# LEDs.net
KiCad netlist of a schematic drawn in Altium Designer
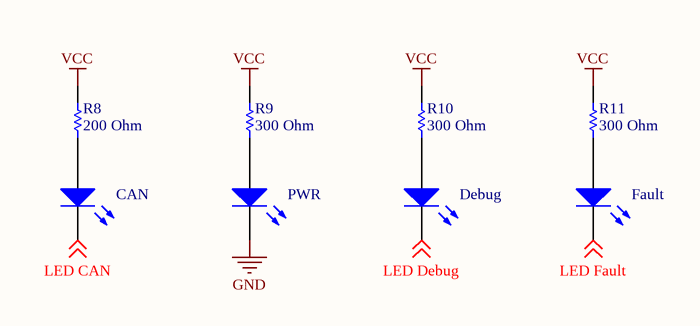
[diagram p0: LEDs.SchDoc]

(export (version "E")
  (design (tool "Eeschema 10.0.6"))
  (components
    (comp (ref "CAN")
      (value "LED")
      (footprint "0805_A")
      (description "Standard 0805 LED")
      (fields (field (name "MANUFACTURER") "Wuerth Elektronik") (field (name "PARTNUMBER") "150080SS75000"))
      (libsource (lib "Husky Robotics Standard Library 2019-2020") (part "LED"))
    )
    (comp (ref "Debug")
      (value "LED")
      (footprint "0805_A")
      (description "Standard 0805 LED")
      (libsource (lib "Husky Robotics Standard Library 2019-2020") (part "LED"))
    )
    (comp (ref "Fault")
      (value "LED")
      (footprint "0805_A")
      (description "Standard 0805 LED")
      (fields (field (name "MANUFACTURER") "Wuerth Elektronik") (field (name "PARTNUMBER") "150080SS75000"))
      (libsource (lib "Husky Robotics Standard Library 2019-2020") (part "LED"))
    )
    (comp (ref "PWR")
      (value "LED")
      (footprint "0805_A")
      (description "Standard 0805 LED")
      (libsource (lib "Husky Robotics Standard Library 2019-2020") (part "LED"))
    )
    (comp (ref "R8")
      (value "200 Ohm")
      (footprint "RESC0805(2012)_N")
      (description "Generic 0805 Resistor")
      (fields (field (name "TOLERANCE") "5 %") (field (name "POWER") "0.125 W"))
      (libsource (lib "Husky Robotics Standard Library 2019-2020") (part "Resistor 0805"))
    )
    (comp (ref "R9")
      (value "300 Ohm")
      (footprint "RESC0805(2012)_N")
      (description "Generic 0805 Resistor")
      (fields (field (name "TOLERANCE") "5 %") (field (name "POWER") "0.125 W"))
      (libsource (lib "Husky Robotics Standard Library 2019-2020") (part "Resistor 0805"))
    )
    (comp (ref "R10")
      (value "300 Ohm")
      (footprint "RESC0805(2012)_N")
      (description "Generic 0805 Resistor")
      (fields (field (name "TOLERANCE") "5 %") (field (name "POWER") "0.125 W"))
      (libsource (lib "Husky Robotics Standard Library 2019-2020") (part "Resistor 0805"))
    )
    (comp (ref "R11")
      (value "300 Ohm")
      (footprint "RESC0805(2012)_N")
      (description "Generic 0805 Resistor")
      (fields (field (name "TOLERANCE") "5 %") (field (name "POWER") "0.125 W"))
      (libsource (lib "Husky Robotics Standard Library 2019-2020") (part "Resistor 0805"))
    )
  )
  (nets
    (net (code "1") (name "GND") (class "Default")
      (node (ref "PWR") (pin "1") (pinfunction "K_1") (pintype "passive"))
    )
    (net (code "2") (name "LED CAN") (class "Default")
      (node (ref "CAN") (pin "1") (pinfunction "K_1") (pintype "passive"))
    )
    (net (code "3") (name "LED Debug") (class "Default")
      (node (ref "Debug") (pin "1") (pinfunction "K_1") (pintype "passive"))
    )
    (net (code "4") (name "LED Fault") (class "Default")
      (node (ref "Fault") (pin "1") (pinfunction "K_1") (pintype "passive"))
    )
    (net (code "5") (name "Net-(CAN-A)") (class "Default")
      (node (ref "CAN") (pin "2") (pinfunction "A_2") (pintype "passive"))
      (node (ref "R8") (pin "2") (pinfunction "2_2") (pintype "passive"))
    )
    (net (code "6") (name "Net-(Debug-A)") (class "Default")
      (node (ref "Debug") (pin "2") (pinfunction "A_2") (pintype "passive"))
      (node (ref "R10") (pin "2") (pinfunction "2_2") (pintype "passive"))
    )
    (net (code "7") (name "Net-(Fault-A)") (class "Default")
      (node (ref "Fault") (pin "2") (pinfunction "A_2") (pintype "passive"))
      (node (ref "R11") (pin "2") (pinfunction "2_2") (pintype "passive"))
    )
    (net (code "8") (name "Net-(PWR-A)") (class "Default")
      (node (ref "PWR") (pin "2") (pinfunction "A_2") (pintype "passive"))
      (node (ref "R9") (pin "2") (pinfunction "2_2") (pintype "passive"))
    )
    (net (code "9") (name "VCC") (class "Default")
      (node (ref "R10") (pin "1") (pinfunction "1_1") (pintype "passive"))
      (node (ref "R11") (pin "1") (pinfunction "1_1") (pintype "passive"))
      (node (ref "R8") (pin "1") (pinfunction "1_1") (pintype "passive"))
      (node (ref "R9") (pin "1") (pinfunction "1_1") (pintype "passive"))
    )
  )
)
